# oven-controller-v2.net
KiCad netlist of a schematic drawn in EAGLE
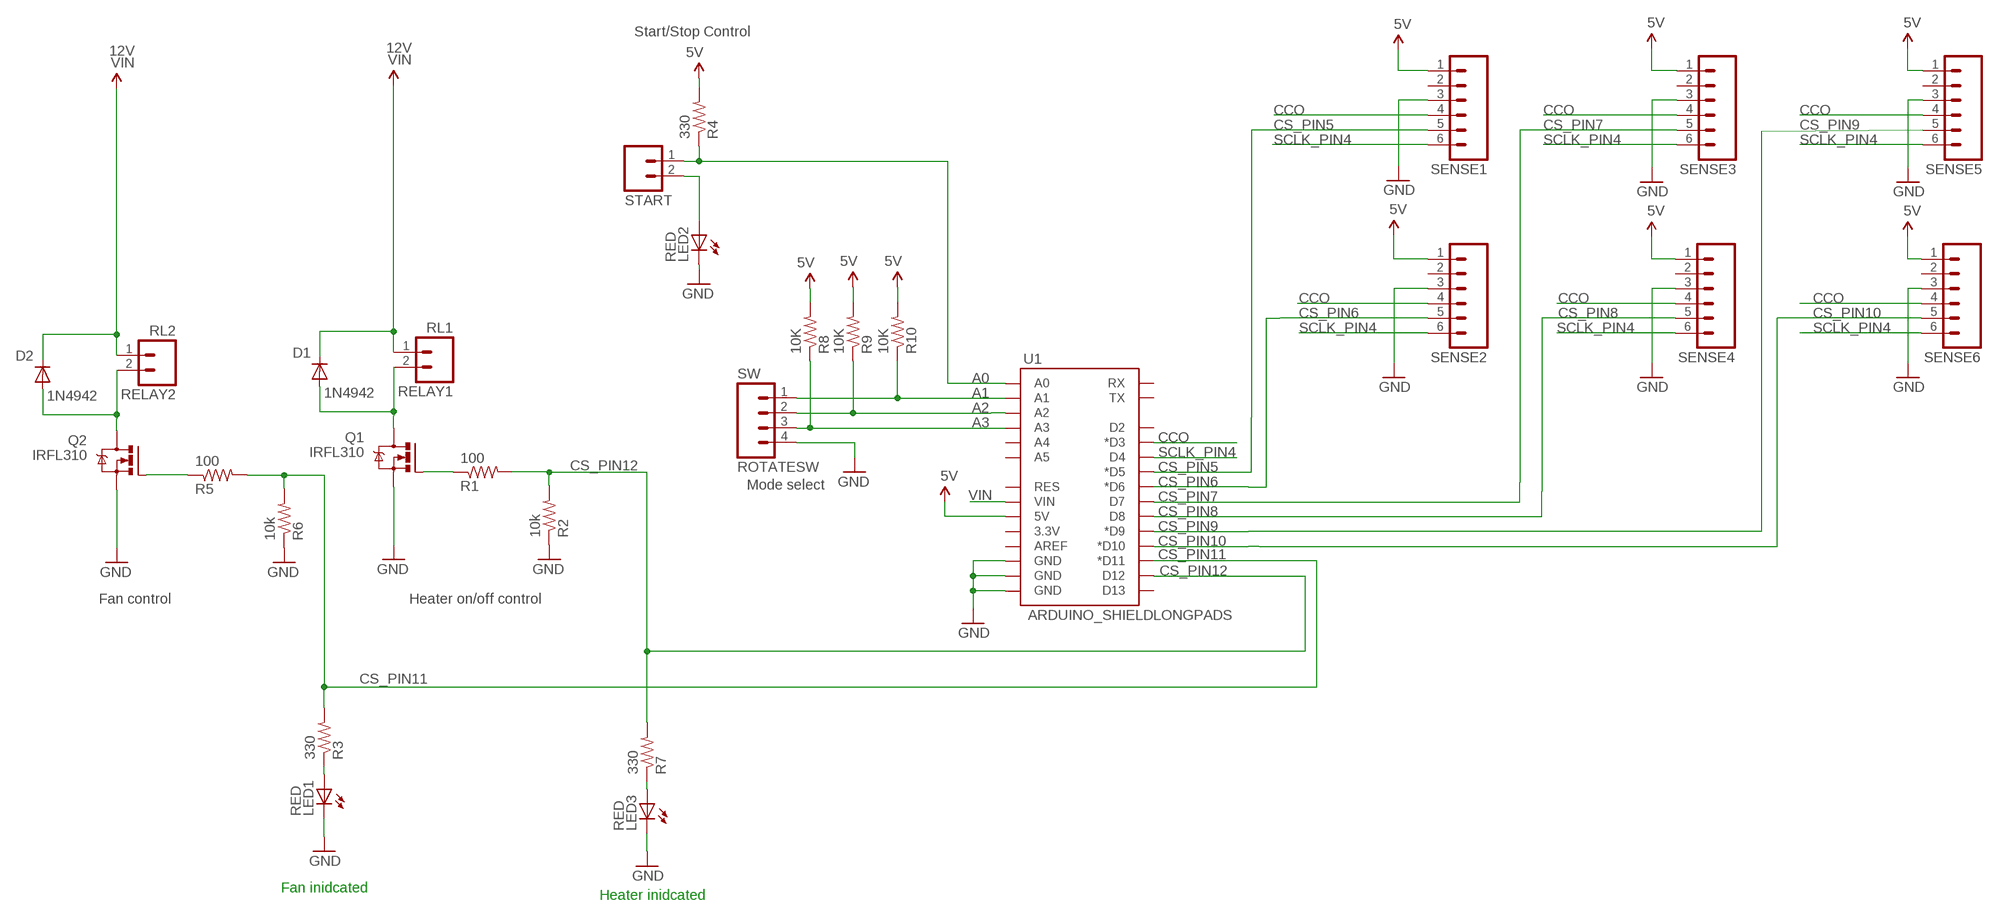
[diagram p0: schematic, sheet 1]

(export (version "E")
  (design (tool "Eeschema 10.0.6"))
  (components
    (comp (ref "D1")
      (value "1N4942")
      (footprint "eagle-import:DO41-10")
      (libsource (lib "eagle-import") (part "1N4942"))
    )
    (comp (ref "D2")
      (value "1N4942")
      (footprint "eagle-import:DO41-10")
      (libsource (lib "eagle-import") (part "1N4942"))
    )
    (comp (ref "LED1")
      (value "RED")
      (footprint "eagle-import:LED5MM")
      (libsource (lib "eagle-import") (part "LED5MM"))
    )
    (comp (ref "LED2")
      (value "RED")
      (footprint "eagle-import:LED5MM")
      (libsource (lib "eagle-import") (part "LED5MM"))
    )
    (comp (ref "LED3")
      (value "RED")
      (footprint "eagle-import:LED5MM")
      (libsource (lib "eagle-import") (part "LED5MM"))
    )
    (comp (ref "Q1")
      (value "IRFL310")
      (footprint "eagle-import:TO220BV")
      (libsource (lib "eagle-import") (part "IRF520"))
    )
    (comp (ref "Q2")
      (value "IRFL310")
      (footprint "eagle-import:TO220BV")
      (libsource (lib "eagle-import") (part "IRF520"))
    )
    (comp (ref "R1")
      (value "100")
      (footprint "eagle-import:AXIAL-0.3")
      (libsource (lib "eagle-import") (part "RESISTORAXIAL-0.3"))
    )
    (comp (ref "R2")
      (value "10k")
      (footprint "eagle-import:AXIAL-0.3")
      (libsource (lib "eagle-import") (part "RESISTORAXIAL-0.3"))
    )
    (comp (ref "R3")
      (value "330")
      (footprint "eagle-import:AXIAL-0.3")
      (libsource (lib "eagle-import") (part "RESISTORAXIAL-0.3"))
    )
    (comp (ref "R4")
      (value "330")
      (footprint "eagle-import:AXIAL-0.3")
      (libsource (lib "eagle-import") (part "RESISTORAXIAL-0.3"))
    )
    (comp (ref "R5")
      (value "100")
      (footprint "eagle-import:AXIAL-0.3")
      (libsource (lib "eagle-import") (part "RESISTORAXIAL-0.3"))
    )
    (comp (ref "R6")
      (value "10k")
      (footprint "eagle-import:AXIAL-0.3")
      (libsource (lib "eagle-import") (part "RESISTORAXIAL-0.3"))
    )
    (comp (ref "R7")
      (value "330")
      (footprint "eagle-import:AXIAL-0.3")
      (libsource (lib "eagle-import") (part "RESISTORAXIAL-0.3"))
    )
    (comp (ref "R8")
      (value "10K")
      (footprint "eagle-import:AXIAL-0.3")
      (libsource (lib "eagle-import") (part "RESISTORAXIAL-0.3"))
    )
    (comp (ref "R9")
      (value "10K")
      (footprint "eagle-import:AXIAL-0.3")
      (libsource (lib "eagle-import") (part "RESISTORAXIAL-0.3"))
    )
    (comp (ref "R10")
      (value "10K")
      (footprint "eagle-import:AXIAL-0.3")
      (libsource (lib "eagle-import") (part "RESISTORAXIAL-0.3"))
    )
    (comp (ref "RELAY1")
      (value "RL1")
      (footprint "eagle-import:SCREWTERMINAL-3.5MM-2_LOCK")
      (libsource (lib "eagle-import") (part "M023.5MM_LOCK"))
    )
    (comp (ref "RELAY2")
      (value "RL2")
      (footprint "eagle-import:SCREWTERMINAL-3.5MM-2_LOCK")
      (libsource (lib "eagle-import") (part "M023.5MM_LOCK"))
    )
    (comp (ref "ROTATESW")
      (value "SW")
      (footprint "eagle-import:1X04_LOCK_LONGPADS")
      (libsource (lib "eagle-import") (part "M04LOCK_LONGPADS"))
    )
    (comp (ref "SENSE1")
      (value "M06LOCK_LONGPADS")
      (footprint "eagle-import:1X06_LOCK_LONGPADS")
      (libsource (lib "eagle-import") (part "M06LOCK_LONGPADS"))
    )
    (comp (ref "SENSE2")
      (value "M06LOCK_LONGPADS")
      (footprint "eagle-import:1X06_LOCK_LONGPADS")
      (libsource (lib "eagle-import") (part "M06LOCK_LONGPADS"))
    )
    (comp (ref "SENSE3")
      (value "M06LOCK_LONGPADS")
      (footprint "eagle-import:1X06_LOCK_LONGPADS")
      (libsource (lib "eagle-import") (part "M06LOCK_LONGPADS"))
    )
    (comp (ref "SENSE4")
      (value "M06LOCK_LONGPADS")
      (footprint "eagle-import:1X06_LOCK_LONGPADS")
      (libsource (lib "eagle-import") (part "M06LOCK_LONGPADS"))
    )
    (comp (ref "SENSE5")
      (value "M06LOCK_LONGPADS")
      (footprint "eagle-import:1X06_LOCK_LONGPADS")
      (libsource (lib "eagle-import") (part "M06LOCK_LONGPADS"))
    )
    (comp (ref "SENSE6")
      (value "M06LOCK_LONGPADS")
      (footprint "eagle-import:1X06_LOCK_LONGPADS")
      (libsource (lib "eagle-import") (part "M06LOCK_LONGPADS"))
    )
    (comp (ref "START")
      (value "M023.5MM_LOCK")
      (footprint "eagle-import:SCREWTERMINAL-3.5MM-2_LOCK")
      (libsource (lib "eagle-import") (part "M023.5MM_LOCK"))
    )
    (comp (ref "U1")
      (value "ARDUINO_SHIELDLONGPADS")
      (footprint "eagle-import:DUEMILANOVE_SHIELD_LONGPADS")
      (libsource (lib "eagle-import") (part "ARDUINO_SHIELDLONGPADS"))
    )
  )
  (nets
    (net (code "1") (name "/A0") (class "Default")
      (node (ref "R4") (pin "P$1") (pinfunction "1_P$1") (pintype "passive"))
      (node (ref "START") (pin "1") (pinfunction "1_1") (pintype "passive"))
      (node (ref "U1") (pin "A0") (pinfunction "A0_A0") (pintype "bidirectional"))
    )
    (net (code "2") (name "/A1") (class "Default")
      (node (ref "R10") (pin "P$1") (pinfunction "1_P$1") (pintype "passive"))
      (node (ref "ROTATESW") (pin "1") (pinfunction "1_1") (pintype "passive"))
      (node (ref "U1") (pin "A1") (pinfunction "A1_A1") (pintype "bidirectional"))
    )
    (net (code "3") (name "/A2") (class "Default")
      (node (ref "R9") (pin "P$1") (pinfunction "1_P$1") (pintype "passive"))
      (node (ref "ROTATESW") (pin "2") (pinfunction "2_2") (pintype "passive"))
      (node (ref "U1") (pin "A2") (pinfunction "A2_A2") (pintype "bidirectional"))
    )
    (net (code "4") (name "/A3") (class "Default")
      (node (ref "R8") (pin "P$1") (pinfunction "1_P$1") (pintype "passive"))
      (node (ref "ROTATESW") (pin "3") (pinfunction "3_3") (pintype "passive"))
      (node (ref "U1") (pin "A3") (pinfunction "A3_A3") (pintype "bidirectional"))
    )
    (net (code "5") (name "/CCO") (class "Default")
      (node (ref "SENSE1") (pin "4") (pinfunction "4_4") (pintype "passive"))
      (node (ref "SENSE2") (pin "4") (pinfunction "4_4") (pintype "passive"))
      (node (ref "SENSE3") (pin "4") (pinfunction "4_4") (pintype "passive"))
      (node (ref "SENSE4") (pin "4") (pinfunction "4_4") (pintype "passive"))
      (node (ref "SENSE5") (pin "4") (pinfunction "4_4") (pintype "passive"))
      (node (ref "SENSE6") (pin "4") (pinfunction "4_4") (pintype "passive"))
      (node (ref "U1") (pin "D3") (pinfunction "*D3_D3") (pintype "bidirectional"))
    )
    (net (code "6") (name "/CS_PIN5") (class "Default")
      (node (ref "SENSE1") (pin "5") (pinfunction "5_5") (pintype "passive"))
      (node (ref "U1") (pin "D5") (pinfunction "*D5_D5") (pintype "bidirectional"))
    )
    (net (code "7") (name "/CS_PIN6") (class "Default")
      (node (ref "SENSE2") (pin "5") (pinfunction "5_5") (pintype "passive"))
      (node (ref "U1") (pin "D6") (pinfunction "*D6_D6") (pintype "bidirectional"))
    )
    (net (code "8") (name "/CS_PIN7") (class "Default")
      (node (ref "SENSE3") (pin "5") (pinfunction "5_5") (pintype "passive"))
      (node (ref "U1") (pin "D7") (pinfunction "D7_D7") (pintype "bidirectional"))
    )
    (net (code "9") (name "/CS_PIN8") (class "Default")
      (node (ref "SENSE4") (pin "5") (pinfunction "5_5") (pintype "passive"))
      (node (ref "U1") (pin "D8") (pinfunction "D8_D8") (pintype "bidirectional"))
    )
    (net (code "10") (name "/CS_PIN9") (class "Default")
      (node (ref "SENSE5") (pin "5") (pinfunction "5_5") (pintype "passive"))
      (node (ref "U1") (pin "D9") (pinfunction "*D9_D9") (pintype "bidirectional"))
    )
    (net (code "11") (name "/CS_PIN10") (class "Default")
      (node (ref "SENSE6") (pin "5") (pinfunction "5_5") (pintype "passive"))
      (node (ref "U1") (pin "D10") (pinfunction "*D10_D10") (pintype "bidirectional"))
    )
    (net (code "12") (name "/CS_PIN11") (class "Default")
      (node (ref "R3") (pin "P$2") (pinfunction "2_P$2") (pintype "passive"))
      (node (ref "R5") (pin "P$2") (pinfunction "2_P$2") (pintype "passive"))
      (node (ref "R6") (pin "P$2") (pinfunction "2_P$2") (pintype "passive"))
      (node (ref "U1") (pin "D11") (pinfunction "*D11_D11") (pintype "bidirectional"))
    )
    (net (code "13") (name "/CS_PIN12") (class "Default")
      (node (ref "R1") (pin "P$2") (pinfunction "2_P$2") (pintype "passive"))
      (node (ref "R2") (pin "P$2") (pinfunction "2_P$2") (pintype "passive"))
      (node (ref "R7") (pin "P$2") (pinfunction "2_P$2") (pintype "passive"))
      (node (ref "U1") (pin "D12") (pinfunction "D12_D12") (pintype "bidirectional"))
    )
    (net (code "14") (name "/SCLK_PIN4") (class "Default")
      (node (ref "SENSE1") (pin "6") (pinfunction "6_6") (pintype "passive"))
      (node (ref "SENSE2") (pin "6") (pinfunction "6_6") (pintype "passive"))
      (node (ref "SENSE3") (pin "6") (pinfunction "6_6") (pintype "passive"))
      (node (ref "SENSE4") (pin "6") (pinfunction "6_6") (pintype "passive"))
      (node (ref "SENSE5") (pin "6") (pinfunction "6_6") (pintype "passive"))
      (node (ref "SENSE6") (pin "6") (pinfunction "6_6") (pintype "passive"))
      (node (ref "U1") (pin "D4") (pinfunction "D4_D4") (pintype "bidirectional"))
    )
    (net (code "15") (name "5V") (class "Default")
      (node (ref "R10") (pin "P$2") (pinfunction "2_P$2") (pintype "passive"))
      (node (ref "R4") (pin "P$2") (pinfunction "2_P$2") (pintype "passive"))
      (node (ref "R8") (pin "P$2") (pinfunction "2_P$2") (pintype "passive"))
      (node (ref "R9") (pin "P$2") (pinfunction "2_P$2") (pintype "passive"))
      (node (ref "SENSE1") (pin "1") (pinfunction "1_1") (pintype "passive"))
      (node (ref "SENSE2") (pin "1") (pinfunction "1_1") (pintype "passive"))
      (node (ref "SENSE3") (pin "1") (pinfunction "1_1") (pintype "passive"))
      (node (ref "SENSE4") (pin "1") (pinfunction "1_1") (pintype "passive"))
      (node (ref "SENSE5") (pin "1") (pinfunction "1_1") (pintype "passive"))
      (node (ref "SENSE6") (pin "1") (pinfunction "1_1") (pintype "passive"))
      (node (ref "U1") (pin "5V") (pinfunction "5V_5V") (pintype "bidirectional"))
    )
    (net (code "16") (name "GND") (class "Default")
      (node (ref "LED1") (pin "K") (pinfunction "C_K") (pintype "passive"))
      (node (ref "LED2") (pin "K") (pinfunction "C_K") (pintype "passive"))
      (node (ref "LED3") (pin "K") (pinfunction "C_K") (pintype "passive"))
      (node (ref "Q1") (pin "S") (pinfunction "S_S") (pintype "passive"))
      (node (ref "Q2") (pin "S") (pinfunction "S_S") (pintype "passive"))
      (node (ref "R2") (pin "P$1") (pinfunction "1_P$1") (pintype "passive"))
      (node (ref "R6") (pin "P$1") (pinfunction "1_P$1") (pintype "passive"))
      (node (ref "ROTATESW") (pin "4") (pinfunction "4_4") (pintype "passive"))
      (node (ref "SENSE1") (pin "3") (pinfunction "3_3") (pintype "passive"))
      (node (ref "SENSE2") (pin "3") (pinfunction "3_3") (pintype "passive"))
      (node (ref "SENSE3") (pin "3") (pinfunction "3_3") (pintype "passive"))
      (node (ref "SENSE4") (pin "3") (pinfunction "3_3") (pintype "passive"))
      (node (ref "SENSE5") (pin "3") (pinfunction "3_3") (pintype "passive"))
      (node (ref "SENSE6") (pin "3") (pinfunction "3_3") (pintype "passive"))
      (node (ref "U1") (pin "GND@0") (pinfunction "GND_GND@0") (pintype "bidirectional"))
      (node (ref "U1") (pin "GND@1") (pinfunction "GND_GND@1") (pintype "bidirectional"))
      (node (ref "U1") (pin "GND@2") (pinfunction "GND_GND@2") (pintype "bidirectional"))
    )
    (net (code "17") (name "Net-(D1-PadA)") (class "Default")
      (node (ref "D1") (pin "A") (pinfunction "A_A") (pintype "passive"))
      (node (ref "Q1") (pin "D") (pinfunction "D_D") (pintype "passive"))
      (node (ref "RELAY1") (pin "2") (pinfunction "2_2") (pintype "passive"))
    )
    (net (code "18") (name "Net-(D2-PadA)") (class "Default")
      (node (ref "D2") (pin "A") (pinfunction "A_A") (pintype "passive"))
      (node (ref "Q2") (pin "D") (pinfunction "D_D") (pintype "passive"))
      (node (ref "RELAY2") (pin "2") (pinfunction "2_2") (pintype "passive"))
    )
    (net (code "19") (name "Net-(LED2-PadA)") (class "Default")
      (node (ref "LED2") (pin "A") (pinfunction "A_A") (pintype "passive"))
      (node (ref "START") (pin "2") (pinfunction "2_2") (pintype "passive"))
    )
    (net (code "20") (name "Net-(R1-1)") (class "Default")
      (node (ref "Q1") (pin "G") (pinfunction "G_G") (pintype "passive"))
      (node (ref "R1") (pin "P$1") (pinfunction "1_P$1") (pintype "passive"))
    )
    (net (code "21") (name "Net-(R3-1)") (class "Default")
      (node (ref "LED1") (pin "A") (pinfunction "A_A") (pintype "passive"))
      (node (ref "R3") (pin "P$1") (pinfunction "1_P$1") (pintype "passive"))
    )
    (net (code "22") (name "Net-(R5-1)") (class "Default")
      (node (ref "Q2") (pin "G") (pinfunction "G_G") (pintype "passive"))
      (node (ref "R5") (pin "P$1") (pinfunction "1_P$1") (pintype "passive"))
    )
    (net (code "23") (name "Net-(R7-1)") (class "Default")
      (node (ref "LED3") (pin "A") (pinfunction "A_A") (pintype "passive"))
      (node (ref "R7") (pin "P$1") (pinfunction "1_P$1") (pintype "passive"))
    )
    (net (code "24") (name "VIN") (class "Default")
      (node (ref "D1") (pin "C") (pinfunction "C_C") (pintype "passive"))
      (node (ref "D2") (pin "C") (pinfunction "C_C") (pintype "passive"))
      (node (ref "RELAY1") (pin "1") (pinfunction "1_1") (pintype "passive"))
      (node (ref "RELAY2") (pin "1") (pinfunction "1_1") (pintype "passive"))
      (node (ref "U1") (pin "VIN") (pinfunction "VIN_VIN") (pintype "bidirectional"))
    )
    (net (code "25") (name "unconnected-(SENSE1-Pad2)") (class "Default")
      (node (ref "SENSE1") (pin "2") (pinfunction "2_2") (pintype "passive"))
    )
    (net (code "26") (name "unconnected-(SENSE2-Pad2)") (class "Default")
      (node (ref "SENSE2") (pin "2") (pinfunction "2_2") (pintype "passive"))
    )
    (net (code "27") (name "unconnected-(SENSE3-Pad2)") (class "Default")
      (node (ref "SENSE3") (pin "2") (pinfunction "2_2") (pintype "passive"))
    )
    (net (code "28") (name "unconnected-(SENSE4-Pad2)") (class "Default")
      (node (ref "SENSE4") (pin "2") (pinfunction "2_2") (pintype "passive"))
    )
    (net (code "29") (name "unconnected-(SENSE5-Pad2)") (class "Default")
      (node (ref "SENSE5") (pin "2") (pinfunction "2_2") (pintype "passive"))
    )
    (net (code "30") (name "unconnected-(SENSE6-Pad2)") (class "Default")
      (node (ref "SENSE6") (pin "2") (pinfunction "2_2") (pintype "passive"))
    )
    (net (code "31") (name "unconnected-(U1-Pad3.3V)") (class "Default")
      (node (ref "U1") (pin "3.3V") (pinfunction "3.3V_3.3V") (pintype "bidirectional"))
    )
    (net (code "32") (name "unconnected-(U1-PadA4)") (class "Default")
      (node (ref "U1") (pin "A4") (pinfunction "A4_A4") (pintype "bidirectional"))
    )
    (net (code "33") (name "unconnected-(U1-PadA5)") (class "Default")
      (node (ref "U1") (pin "A5") (pinfunction "A5_A5") (pintype "bidirectional"))
    )
    (net (code "34") (name "unconnected-(U1-PadAREF)") (class "Default")
      (node (ref "U1") (pin "AREF") (pinfunction "AREF_AREF") (pintype "bidirectional"))
    )
    (net (code "35") (name "unconnected-(U1-PadD2)") (class "Default")
      (node (ref "U1") (pin "D2") (pinfunction "D2_D2") (pintype "bidirectional"))
    )
    (net (code "36") (name "unconnected-(U1-PadD13)") (class "Default")
      (node (ref "U1") (pin "D13") (pinfunction "D13_D13") (pintype "bidirectional"))
    )
    (net (code "37") (name "unconnected-(U1-PadRES)") (class "Default")
      (node (ref "U1") (pin "RES") (pinfunction "RES_RES") (pintype "bidirectional"))
    )
    (net (code "38") (name "unconnected-(U1-PadRX)") (class "Default")
      (node (ref "U1") (pin "RX") (pinfunction "RX_RX") (pintype "bidirectional"))
    )
    (net (code "39") (name "unconnected-(U1-PadTX)") (class "Default")
      (node (ref "U1") (pin "TX") (pinfunction "TX_TX") (pintype "bidirectional"))
    )
  )
)
